# sjl.net
KiCad netlist of a schematic drawn in EasyEDA Pro
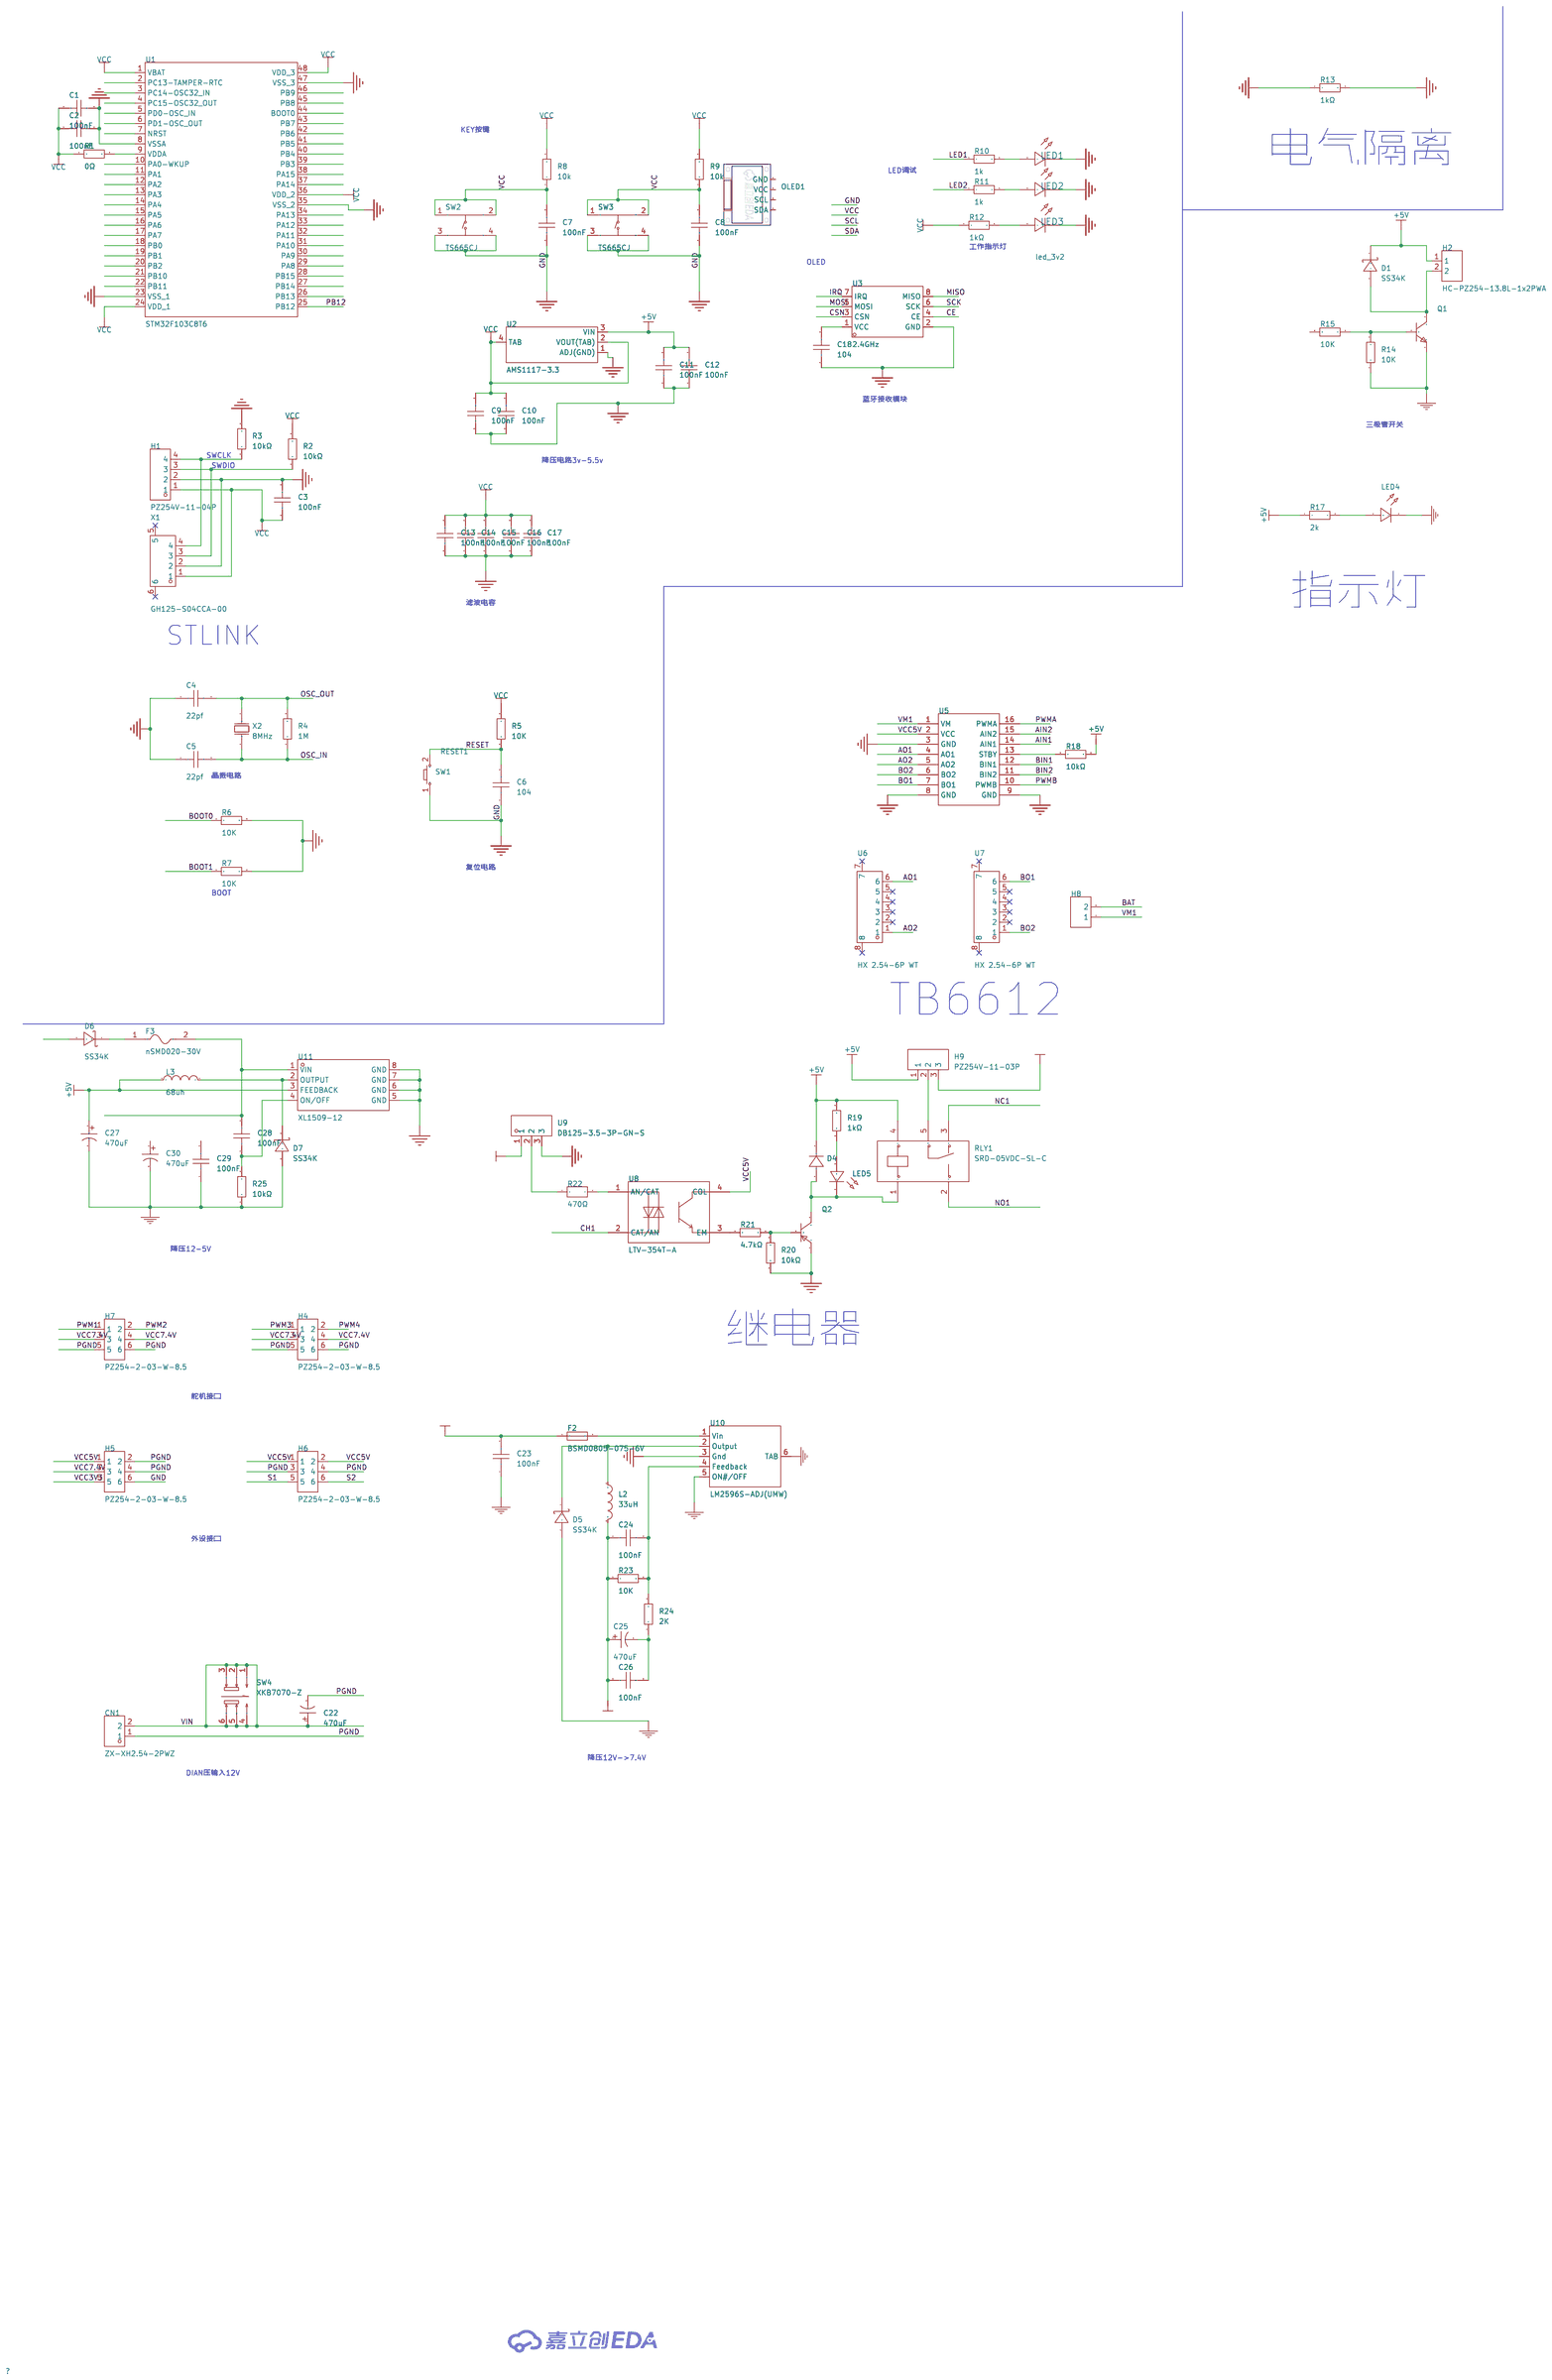
[diagram p0: schematic sheet]

(export (version "E")
  (design (tool "Eeschema 10.0.6"))
  (components
    (comp (ref "C1")
      (value "100nF")
      (footprint "easyedapro:C0603")
      (description "容值:100nF;精度:±10%;额定电压:50V;温度系数:X7R;")
      (fields
        (field (name "Manufacturer Part") "CGA0603X7R104K500JT")
        (field (name "Manufacturer") "HRE(芯声)")
      )
      (libsource (lib "easyedapro") (part "CGA0603X7R104K500JT"))
    )
    (comp (ref "C2")
      (value "100nF")
      (footprint "easyedapro:C0603")
      (description "容值:100nF;精度:±10%;额定电压:50V;温度系数:X7R;")
      (fields
        (field (name "Manufacturer Part") "CGA0603X7R104K500JT")
        (field (name "Manufacturer") "HRE(芯声)")
      )
      (libsource (lib "easyedapro") (part "CGA0603X7R104K500JT"))
    )
    (comp (ref "C3")
      (value "100nF")
      (footprint "easyedapro:C0603")
      (description "容值:100nF;精度:±10%;额定电压:50V;温度系数:X7R;")
      (fields
        (field (name "Manufacturer Part") "CGA0603X7R104K500JT")
        (field (name "Manufacturer") "HRE(芯声)")
      )
      (libsource (lib "easyedapro") (part "CGA0603X7R104K500JT"))
    )
    (comp (ref "C4")
      (value "22pf")
      (footprint "easyedapro:C0603")
      (libsource (lib "easyedapro") (part "CapAcitance"))
    )
    (comp (ref "C5")
      (value "22pf")
      (footprint "easyedapro:C0603")
      (libsource (lib "easyedapro") (part "CapAcitance"))
    )
    (comp (ref "C6")
      (value "104")
      (footprint "easyedapro:C0603")
      (description "容值:100nF;精度:±10%;额定电压:50V;温度系数:X7R;")
      (fields
        (field (name "Manufacturer Part") "CGA0603X7R104K500JT")
        (field (name "Manufacturer") "HRE(芯声)")
      )
      (libsource (lib "easyedapro") (part "CGA0603X7R104K500JT"))
    )
    (comp (ref "C7")
      (value "100nF")
      (footprint "easyedapro:C0603")
      (description "容值:100nF;精度:±10%;额定电压:50V;温度系数:X7R;")
      (fields
        (field (name "Manufacturer Part") "CGA0603X7R104K500JT")
        (field (name "Manufacturer") "HRE(芯声)")
      )
      (libsource (lib "easyedapro") (part "CGA0603X7R104K500JT"))
    )
    (comp (ref "C8")
      (value "100nF")
      (footprint "easyedapro:C0603")
      (description "容值:100nF;精度:±10%;额定电压:50V;温度系数:X7R;")
      (fields
        (field (name "Manufacturer Part") "CGA0603X7R104K500JT")
        (field (name "Manufacturer") "HRE(芯声)")
      )
      (libsource (lib "easyedapro") (part "CGA0603X7R104K500JT"))
    )
    (comp (ref "C9")
      (value "100nF")
      (footprint "easyedapro:C0603")
      (description "容值:100nF;精度:±10%;额定电压:50V;温度系数:X7R;")
      (fields
        (field (name "Manufacturer Part") "CGA0603X7R104K500JT")
        (field (name "Manufacturer") "HRE(芯声)")
      )
      (libsource (lib "easyedapro") (part "CGA0603X7R104K500JT"))
    )
    (comp (ref "C10")
      (value "100nF")
      (footprint "easyedapro:C0603")
      (description "容值:100nF;精度:±10%;额定电压:50V;温度系数:X7R;")
      (fields
        (field (name "Manufacturer Part") "CGA0603X7R104K500JT")
        (field (name "Manufacturer") "HRE(芯声)")
      )
      (libsource (lib "easyedapro") (part "CGA0603X7R104K500JT"))
    )
    (comp (ref "C11")
      (value "100nF")
      (footprint "easyedapro:C0603")
      (description "容值:100nF;精度:±10%;额定电压:50V;温度系数:X7R;")
      (fields
        (field (name "Manufacturer Part") "CGA0603X7R104K500JT")
        (field (name "Manufacturer") "HRE(芯声)")
      )
      (libsource (lib "easyedapro") (part "CGA0603X7R104K500JT"))
    )
    (comp (ref "C12")
      (value "100nF")
      (footprint "easyedapro:C0603")
      (description "容值:100nF;精度:±10%;额定电压:50V;温度系数:X7R;")
      (fields
        (field (name "Manufacturer Part") "CGA0603X7R104K500JT")
        (field (name "Manufacturer") "HRE(芯声)")
      )
      (libsource (lib "easyedapro") (part "CGA0603X7R104K500JT"))
    )
    (comp (ref "C13")
      (value "100nF")
      (footprint "easyedapro:C0603")
      (description "容值:100nF;精度:±10%;额定电压:50V;温度系数:X7R;")
      (fields
        (field (name "Manufacturer Part") "CGA0603X7R104K500JT")
        (field (name "Manufacturer") "HRE(芯声)")
      )
      (libsource (lib "easyedapro") (part "CGA0603X7R104K500JT"))
    )
    (comp (ref "C14")
      (value "100nF")
      (footprint "easyedapro:C0603")
      (description "容值:100nF;精度:±10%;额定电压:50V;温度系数:X7R;")
      (fields
        (field (name "Manufacturer Part") "CGA0603X7R104K500JT")
        (field (name "Manufacturer") "HRE(芯声)")
      )
      (libsource (lib "easyedapro") (part "CGA0603X7R104K500JT"))
    )
    (comp (ref "C15")
      (value "100nF")
      (footprint "easyedapro:C0603")
      (description "容值:100nF;精度:±10%;额定电压:50V;温度系数:X7R;")
      (fields
        (field (name "Manufacturer Part") "CGA0603X7R104K500JT")
        (field (name "Manufacturer") "HRE(芯声)")
      )
      (libsource (lib "easyedapro") (part "CGA0603X7R104K500JT"))
    )
    (comp (ref "C16")
      (value "100nF")
      (footprint "easyedapro:C0603")
      (description "容值:100nF;精度:±10%;额定电压:50V;温度系数:X7R;")
      (fields
        (field (name "Manufacturer Part") "CGA0603X7R104K500JT")
        (field (name "Manufacturer") "HRE(芯声)")
      )
      (libsource (lib "easyedapro") (part "CGA0603X7R104K500JT"))
    )
    (comp (ref "C17")
      (value "100nF")
      (footprint "easyedapro:C0603")
      (description "容值:100nF;精度:±10%;额定电压:50V;温度系数:X7R;")
      (fields
        (field (name "Manufacturer Part") "CGA0603X7R104K500JT")
        (field (name "Manufacturer") "HRE(芯声)")
      )
      (libsource (lib "easyedapro") (part "CGA0603X7R104K500JT"))
    )
    (comp (ref "C18")
      (value "104")
      (footprint "easyedapro:C0603")
      (description "容值:100nF;精度:±10%;额定电压:50V;温度系数:X7R;")
      (fields
        (field (name "Manufacturer Part") "CGA0603X7R104K500JT")
        (field (name "Manufacturer") "HRE(芯声)")
      )
      (libsource (lib "easyedapro") (part "CGA0603X7R104K500JT"))
    )
    (comp (ref "C22")
      (value "470uF")
      (footprint "easyedapro:CAP-SMD_BD10.0-L10.3-W10.3-FD")
      (description "容值:470uF;精度:±20%;额定电压:25V;纹波电流:286mA@120Hz;等效串联电阻(ESR):-;")
      (fields (field (name "Manufacturer Part") "RVT1E471M1010") (field (name "Manufacturer") "ROQANG(容强)"))
      (libsource (lib "easyedapro") (part "RVT1E471M1010"))
    )
    (comp (ref "C23")
      (value "100nF")
      (footprint "easyedapro:C0603")
      (libsource (lib "easyedapro") (part "CapAcitance"))
    )
    (comp (ref "C24")
      (value "100nF")
      (footprint "easyedapro:C0603")
      (libsource (lib "easyedapro") (part "CapAcitance"))
    )
    (comp (ref "C25")
      (value "470uF")
      (footprint "easyedapro:CAP-SMD_BD10.0-L10.3-W10.3-FD")
      (description "容值:470uF;精度:±20%;额定电压:25V;纹波电流:286mA@120Hz;等效串联电阻(ESR):-;")
      (fields (field (name "Manufacturer Part") "RVT1E471M1010") (field (name "Manufacturer") "ROQANG(容强)"))
      (libsource (lib "easyedapro") (part "RVT1E471M1010"))
    )
    (comp (ref "C26")
      (value "100nF")
      (footprint "easyedapro:C0603")
      (libsource (lib "easyedapro") (part "CapAcitance"))
    )
    (comp (ref "C27")
      (value "470uF")
      (footprint "easyedapro:CAP-SMD_BD10.0-L10.3-W10.3-FD")
      (description "容值:470uF;精度:±20%;额定电压:25V;纹波电流:286mA@120Hz;等效串联电阻(ESR):-;")
      (fields (field (name "Manufacturer Part") "RVT1E471M1010") (field (name "Manufacturer") "ROQANG(容强)"))
      (libsource (lib "easyedapro") (part "RVT1E471M1010"))
    )
    (comp (ref "C28")
      (value "100nF")
      (footprint "easyedapro:C0603")
      (libsource (lib "easyedapro") (part "CapAcitance"))
    )
    (comp (ref "C29")
      (value "100nF")
      (footprint "easyedapro:C0603")
      (libsource (lib "easyedapro") (part "CapAcitance"))
    )
    (comp (ref "C30")
      (value "470uF")
      (footprint "easyedapro:CAP-SMD_BD10.0-L10.3-W10.3-FD")
      (description "容值:470uF;精度:±20%;额定电压:25V;纹波电流:286mA@120Hz;等效串联电阻(ESR):-;")
      (fields (field (name "Manufacturer Part") "RVT1E471M1010") (field (name "Manufacturer") "ROQANG(容强)"))
      (libsource (lib "easyedapro") (part "RVT1E471M1010"))
    )
    (comp (ref "CN1")
      (value "ZX-XH2.54-2PWZ")
      (footprint "easyedapro:CONN-TH_2P-P2.50_ZX-XH2.54-2PWZ")
      (fields (field (name "Manufacturer") "Megastar(兆星)"))
      (libsource (lib "easyedapro") (part "ZX-XH2.54-2PWZ"))
    )
    (comp (ref "D1")
      (value "SS34K")
      (footprint "easyedapro:SMA_L4.3-W2.6-LS5.2-RD")
      (description "二极管配置:独立式;直流反向耐压(Vr):40V;平均整流电流(Io):3A;正向压降(Vf):550mV@3A;反向电流(Ir):500uA@40V;")
      (fields (field (name "Manufacturer") "TDD(台冠电子)"))
      (libsource (lib "easyedapro") (part "SS34K"))
    )
    (comp (ref "D4")
      (value "~")
      (footprint "easyedapro:DO_1N4007")
      (libsource (lib "easyedapro") (part "D_1N4007"))
    )
    (comp (ref "D5")
      (value "SS34K")
      (footprint "easyedapro:SMA_L4.3-W2.6-LS5.2-RD")
      (description "二极管配置:独立式;直流反向耐压(Vr):40V;平均整流电流(Io):3A;正向压降(Vf):550mV@3A;反向电流(Ir):500uA@40V;")
      (fields (field (name "Manufacturer") "TDD(台冠电子)"))
      (libsource (lib "easyedapro") (part "SS34K"))
    )
    (comp (ref "D6")
      (value "SS34K")
      (footprint "easyedapro:SMA_L4.3-W2.6-LS5.2-RD")
      (description "二极管配置:独立式;直流反向耐压(Vr):40V;平均整流电流(Io):3A;正向压降(Vf):550mV@3A;反向电流(Ir):500uA@40V;")
      (fields (field (name "Manufacturer") "TDD(台冠电子)"))
      (libsource (lib "easyedapro") (part "SS34K"))
    )
    (comp (ref "D7")
      (value "SS34K")
      (footprint "easyedapro:SMA_L4.3-W2.6-LS5.2-RD")
      (description "二极管配置:独立式;直流反向耐压(Vr):40V;平均整流电流(Io):3A;正向压降(Vf):550mV@3A;反向电流(Ir):500uA@40V;")
      (fields (field (name "Manufacturer") "TDD(台冠电子)"))
      (libsource (lib "easyedapro") (part "SS34K"))
    )
    (comp (ref "F2")
      (value "BSMD0805-075-6V")
      (footprint "easyedapro:F0805")
      (description "最大电压:6V;最大电流:40A;保持电流:750mA;跳闸电流:1.5A;")
      (fields (field (name "Manufacturer") "BHFUSE(佰宏)"))
      (libsource (lib "easyedapro") (part "BSMD0805-075-6V"))
    )
    (comp (ref "F3")
      (value "nSMD020-30V")
      (footprint "easyedapro:F1206")
      (description "耐压:30V;最大电流:100A;保持电流(Ih):200mA;跳闸电流:460mA;")
      (fields (field (name "Manufacturer") "台湾陆海"))
      (libsource (lib "easyedapro") (part "nSMD020-30V"))
    )
    (comp (ref "H1")
      (value "PZ254V-11-04P")
      (footprint "easyedapro:HDR-TH_4P-P2.54-V-M")
      (fields (field (name "Manufacturer") "XFCN(兴飞)"))
      (libsource (lib "easyedapro") (part "PZ254V-11-04P_C2691448"))
    )
    (comp (ref "H2")
      (value "HC-PZ254-13.8L-1x2PWA")
      (footprint "easyedapro:HDR-TH_2P-P2.54-H-M-W10.0")
      (fields (field (name "Manufacturer") "HC(虹成电子)"))
      (libsource (lib "easyedapro") (part "HC-PZ254-13.8L-1X2PWA"))
    )
    (comp (ref "H4")
      (value "PZ254-2-03-W-8.5")
      (footprint "easyedapro:HDR-TH_6P-P2.54-H-M-R2-C3-S2.54-W12.3-N")
      (fields (field (name "Manufacturer") "HCTL(华灿天禄)"))
      (libsource (lib "easyedapro") (part "PZ254-2-03-W-8.5"))
    )
    (comp (ref "H5")
      (value "PZ254-2-03-W-8.5")
      (footprint "easyedapro:HDR-TH_6P-P2.54-H-M-R2-C3-S2.54-W12.3-N")
      (fields (field (name "Manufacturer") "HCTL(华灿天禄)"))
      (libsource (lib "easyedapro") (part "PZ254-2-03-W-8.5"))
    )
    (comp (ref "H6")
      (value "PZ254-2-03-W-8.5")
      (footprint "easyedapro:HDR-TH_6P-P2.54-H-M-R2-C3-S2.54-W12.3-N")
      (fields (field (name "Manufacturer") "HCTL(华灿天禄)"))
      (libsource (lib "easyedapro") (part "PZ254-2-03-W-8.5"))
    )
    (comp (ref "H7")
      (value "PZ254-2-03-W-8.5")
      (footprint "easyedapro:HDR-TH_6P-P2.54-H-M-R2-C3-S2.54-W12.3-N")
      (fields (field (name "Manufacturer") "HCTL(华灿天禄)"))
      (libsource (lib "easyedapro") (part "PZ254-2-03-W-8.5"))
    )
    (comp (ref "H8")
      (value "~")
      (footprint "easyedapro:HDR-TH_2P-P2.54-V-F")
      (libsource (lib "easyedapro") (part "Header-Female-2.54_1x2"))
    )
    (comp (ref "H9")
      (value "PZ254V-11-03P")
      (footprint "easyedapro:HDR-TH_3P-P2.54-V-M")
      (fields (field (name "Manufacturer") "XFCN(兴飞)"))
      (libsource (lib "easyedapro") (part "PZ254V-11-03P_C2937625"))
    )
    (comp (ref "L2")
      (value "33uH")
      (footprint "easyedapro:L0603")
      (libsource (lib "easyedapro") (part "SDFL1608S100KTF"))
    )
    (comp (ref "L3")
      (value "68uh")
      (footprint "easyedapro:L0603")
      (libsource (lib "easyedapro") (part "SDFL1608S100KTF"))
    )
    (comp (ref "LED1")
      (value "~")
      (footprint "easyedapro:LED_0603")
      (libsource (lib "easyedapro") (part "LED_R"))
    )
    (comp (ref "LED2")
      (value "~")
      (footprint "easyedapro:LED_0603")
      (libsource (lib "easyedapro") (part "LED_R"))
    )
    (comp (ref "LED3")
      (value "led_3v2")
      (footprint "easyedapro:LED_0603")
      (libsource (lib "easyedapro") (part "LED_R"))
    )
    (comp (ref "LED4")
      (value "~")
      (footprint "easyedapro:LED_TH-3mm")
      (libsource (lib "easyedapro") (part "LED_TH-R"))
    )
    (comp (ref "LED5")
      (value "~")
      (footprint "easyedapro:LED_TH-3mm")
      (libsource (lib "easyedapro") (part "LED_TH-R"))
    )
    (comp (ref "OLED1")
      (value "~")
      (footprint "easyedapro:0.96OLED_4P")
      (libsource (lib "easyedapro") (part "0.96OLED模块_4P"))
    )
    (comp (ref "Q1")
      (value "~")
      (footprint "easyedapro:S8050_SOT-23")
      (libsource (lib "easyedapro") (part "NPN"))
    )
    (comp (ref "Q2")
      (value "~")
      (footprint "easyedapro:S8550P_SOT")
      (libsource (lib "easyedapro") (part "PNP"))
    )
    (comp (ref "R1")
      (value "0Ω")
      (footprint "easyedapro:R0603")
      (description "电阻类型:厚膜电阻;阻值:0Ω;精度:±1%;功率:100mW;最大工作电压:75V;")
      (fields
        (field (name "Manufacturer Part") "0603WAF0000T5E")
        (field (name "Manufacturer") "UNI-ROYAL(厚声)")
      )
      (libsource (lib "easyedapro") (part "0603WAF0000T5E"))
    )
    (comp (ref "R2")
      (value "10kΩ")
      (footprint "easyedapro:R0603")
      (description "电阻类型:厚膜电阻;阻值:10kΩ;精度:±1%;功率:100mW;最大工作电压:75V;温度系数:±100ppm/°C;")
      (fields
        (field (name "Manufacturer Part") "0603WAF1002T5E")
        (field (name "Manufacturer") "UNI-ROYAL(厚声)")
      )
      (libsource (lib "easyedapro") (part "0603WAF1002T5E"))
    )
    (comp (ref "R3")
      (value "10kΩ")
      (footprint "easyedapro:R0603")
      (description "电阻类型:厚膜电阻;阻值:10kΩ;精度:±1%;功率:100mW;最大工作电压:75V;温度系数:±100ppm/°C;")
      (fields
        (field (name "Manufacturer Part") "0603WAF1002T5E")
        (field (name "Manufacturer") "UNI-ROYAL(厚声)")
      )
      (libsource (lib "easyedapro") (part "0603WAF1002T5E"))
    )
    (comp (ref "R4")
      (value "1M")
      (footprint "easyedapro:R0603")
      (description "电阻类型:厚膜电阻;阻值:0Ω;精度:±1%;功率:100mW;最大工作电压:75V;")
      (fields
        (field (name "Manufacturer Part") "0603WAF0000T5E")
        (field (name "Manufacturer") "UNI-ROYAL(厚声)")
      )
      (libsource (lib "easyedapro") (part "0603WAF0000T5E"))
    )
    (comp (ref "R5")
      (value "10K")
      (footprint "easyedapro:R0603")
      (description "电阻类型:厚膜电阻;阻值:0Ω;精度:±1%;功率:100mW;最大工作电压:75V;")
      (fields
        (field (name "Manufacturer Part") "0603WAF0000T5E")
        (field (name "Manufacturer") "UNI-ROYAL(厚声)")
      )
      (libsource (lib "easyedapro") (part "0603WAF0000T5E"))
    )
    (comp (ref "R6")
      (value "10K")
      (footprint "easyedapro:Res_1/8W")
      (libsource (lib "easyedapro") (part "电阻"))
    )
    (comp (ref "R7")
      (value "10K")
      (footprint "easyedapro:Res_1/8W")
      (libsource (lib "easyedapro") (part "电阻"))
    )
    (comp (ref "R8")
      (value "10k")
      (footprint "easyedapro:R0603")
      (description "电阻类型:厚膜电阻;阻值:0Ω;精度:±1%;功率:100mW;最大工作电压:75V;")
      (fields
        (field (name "Manufacturer Part") "0603WAF0000T5E")
        (field (name "Manufacturer") "UNI-ROYAL(厚声)")
      )
      (libsource (lib "easyedapro") (part "0603WAF0000T5E"))
    )
    (comp (ref "R9")
      (value "10k")
      (footprint "easyedapro:R0603")
      (description "电阻类型:厚膜电阻;阻值:0Ω;精度:±1%;功率:100mW;最大工作电压:75V;")
      (fields
        (field (name "Manufacturer Part") "0603WAF0000T5E")
        (field (name "Manufacturer") "UNI-ROYAL(厚声)")
      )
      (libsource (lib "easyedapro") (part "0603WAF0000T5E"))
    )
    (comp (ref "R10")
      (value "1k")
      (footprint "easyedapro:R0603")
      (description "电阻类型:厚膜电阻;阻值:0Ω;精度:±1%;功率:100mW;最大工作电压:75V;")
      (fields
        (field (name "Manufacturer Part") "0603WAF0000T5E")
        (field (name "Manufacturer") "UNI-ROYAL(厚声)")
      )
      (libsource (lib "easyedapro") (part "0603WAF0000T5E"))
    )
    (comp (ref "R11")
      (value "1k")
      (footprint "easyedapro:R0603")
      (description "电阻类型:厚膜电阻;阻值:0Ω;精度:±1%;功率:100mW;最大工作电压:75V;")
      (fields
        (field (name "Manufacturer Part") "0603WAF0000T5E")
        (field (name "Manufacturer") "UNI-ROYAL(厚声)")
      )
      (libsource (lib "easyedapro") (part "0603WAF0000T5E"))
    )
    (comp (ref "R12")
      (value "1kΩ")
      (footprint "easyedapro:R0603")
      (description "电阻类型:厚膜电阻;阻值:1kΩ;精度:±1%;功率:100mW;最大工作电压:75V;温度系数:±100ppm/°C;")
      (fields
        (field (name "Manufacturer Part") "0603WAF1001T5E")
        (field (name "Manufacturer") "UNI-ROYAL(厚声)")
      )
      (libsource (lib "easyedapro") (part "0603WAF1001T5E"))
    )
    (comp (ref "R13")
      (value "1kΩ")
      (footprint "easyedapro:R0603")
      (description "电阻类型:厚膜电阻;阻值:1kΩ;精度:±1%;功率:100mW;最大工作电压:75V;温度系数:±100ppm/°C;")
      (fields
        (field (name "Manufacturer Part") "0603WAF1001T5E")
        (field (name "Manufacturer") "UNI-ROYAL(厚声)")
      )
      (libsource (lib "easyedapro") (part "0603WAF1001T5E"))
    )
    (comp (ref "R14")
      (value "10K")
      (footprint "easyedapro:Res_1/8W")
      (libsource (lib "easyedapro") (part "电阻"))
    )
    (comp (ref "R15")
      (value "10K")
      (footprint "easyedapro:Res_1/8W")
      (libsource (lib "easyedapro") (part "电阻"))
    )
    (comp (ref "R17")
      (value "2k")
      (footprint "easyedapro:Res_1/8W")
      (libsource (lib "easyedapro") (part "电阻"))
    )
    (comp (ref "R18")
      (value "10kΩ")
      (footprint "easyedapro:R0603")
      (description "电阻类型:厚膜电阻;阻值:10kΩ;精度:±1%;功率:100mW;最大工作电压:75V;温度系数:±100ppm/°C;")
      (fields
        (field (name "Manufacturer Part") "0603WAF1002T5E")
        (field (name "Manufacturer") "UNI-ROYAL(厚声)")
      )
      (libsource (lib "easyedapro") (part "0603WAF1002T5E"))
    )
    (comp (ref "R19")
      (value "1kΩ")
      (footprint "easyedapro:R0603")
      (description "电阻类型:厚膜电阻;阻值:1kΩ;精度:±1%;功率:100mW;最大工作电压:75V;温度系数:±100ppm/°C;")
      (fields
        (field (name "Manufacturer Part") "0603WAF1001T5E")
        (field (name "Manufacturer") "UNI-ROYAL(厚声)")
      )
      (libsource (lib "easyedapro") (part "0603WAF1001T5E"))
    )
    (comp (ref "R20")
      (value "10kΩ")
      (footprint "easyedapro:Res_1/8W")
      (libsource (lib "easyedapro") (part "电阻"))
    )
    (comp (ref "R21")
      (value "4.7kΩ")
      (footprint "easyedapro:R0603")
      (description "电阻类型:厚膜电阻;阻值:4.7kΩ;精度:±1%;功率:100mW;最大工作电压:75V;温度系数:±100ppm/°C;")
      (fields
        (field (name "Manufacturer Part") "0603WAF4701T5E")
        (field (name "Manufacturer") "UNI-ROYAL(厚声)")
      )
      (libsource (lib "easyedapro") (part "0603WAF4701T5E"))
    )
    (comp (ref "R22")
      (value "470Ω")
      (footprint "easyedapro:R0603")
      (description "电阻类型:厚膜电阻;阻值:470Ω;精度:±1%;功率:100mW;温度系数:±100ppm/°C;")
      (fields (field (name "Manufacturer Part") "CR164700F") (field (name "Manufacturer") "Meritek"))
      (libsource (lib "easyedapro") (part "CR164700F"))
    )
    (comp (ref "R23")
      (value "10K")
      (footprint "easyedapro:Res_1/8W")
      (libsource (lib "easyedapro") (part "电阻"))
    )
    (comp (ref "R24")
      (value "2K")
      (footprint "easyedapro:R0603")
      (description "电阻类型:厚膜电阻;阻值:4.7kΩ;精度:±1%;功率:100mW;最大工作电压:75V;温度系数:±100ppm/°C;")
      (fields
        (field (name "Manufacturer Part") "0603WAF4701T5E")
        (field (name "Manufacturer") "UNI-ROYAL(厚声)")
      )
      (libsource (lib "easyedapro") (part "0603WAF4701T5E"))
    )
    (comp (ref "R25")
      (value "10kΩ")
      (footprint "easyedapro:Res_1/8W")
      (libsource (lib "easyedapro") (part "电阻"))
    )
    (comp (ref "RLY1")
      (value "SRD-05VDC-SL-C")
      (footprint "easyedapro:RELAY-TH_SRD-XXVDC-XL-C")
      (description "线圈电压:5V;触点形式:一组转换:1C(单刀双掷-转换);触点容量(电阻负载):-;最大切换电压:250V@AC;最大切换电流:15A;")
      (fields (field (name "Manufacturer") "松乐"))
      (libsource (lib "easyedapro") (part "SRD-05VDC-SL-C"))
    )
    (comp (ref "SW1")
      (value "RESET1")
      (footprint "easyedapro:Key_SMD_3x4x2")
      (libsource (lib "easyedapro") (part "轻触按键x2"))
    )
    (comp (ref "SW2")
      (value "TS665CJ")
      (footprint "easyedapro:SW-TH_4P-L6.0-W6.0-P4.50-LS6.5")
      (description "电路结构:单刀单掷;按钮形状:圆形按钮;安装方式:直插;开关长度:6mm;开关宽度:6mm;开关高度:5mm;触点电流:50mA;额定电压(DC):12V;带灯:-;机械寿命:-;")
      (fields (field (name "Manufacturer") "SHOU HAN(首韩)"))
      (libsource (lib "easyedapro") (part "TS665CJ"))
    )
    (comp (ref "SW3")
      (value "TS665CJ")
      (footprint "easyedapro:SW-TH_4P-L6.0-W6.0-P4.50-LS6.5")
      (description "电路结构:单刀单掷;按钮形状:圆形按钮;安装方式:直插;开关长度:6mm;开关宽度:6mm;开关高度:5mm;触点电流:50mA;额定电压(DC):12V;带灯:-;机械寿命:-;")
      (fields (field (name "Manufacturer") "SHOU HAN(首韩)"))
      (libsource (lib "easyedapro") (part "TS665CJ"))
    )
    (comp (ref "SW4")
      (value "XKB7070-Z")
      (footprint "easyedapro:SW-TH_6P-L7.0-W7.0-P2.00")
      (description "自锁/无锁:自锁;安装方式:直插;触点电流:100mA;额定电压 (AC):250V;额定电压 (DC):30V;带灯:不带;作用力:160gf;机械寿命:10万次;")
      (fields (field (name "Manufacturer") "XKB Connectivity(中国星坤)"))
      (libsource (lib "easyedapro") (part "XKB7070-Z"))
    )
    (comp (ref "U1")
      (value "STM32F103C8T6")
      (footprint "easyedapro:LQFP-48_L7.0-W7.0-P0.50-LS9.0-BL")
      (description "CPU内核:ARM-M3;CPU最大主频:72MHz;应用领域:-;")
      (fields (field (name "Manufacturer") "ST(意法半导体)"))
      (libsource (lib "easyedapro") (part "STM32F103C8T6"))
    )
    (comp (ref "U2")
      (value "AMS1117-3.3")
      (footprint "easyedapro:SOT-223-4_L6.5-W3.5-P2.30-LS7.0-BR")
      (description "输出类型:固定;工作电压:12V;输出电压:3.3V;输出电流:1A;电源纹波抑制比(PSRR):60dB@(120Hz);输出极性:正极;")
      (fields (field (name "Manufacturer") "UMW(友台半导体)"))
      (libsource (lib "easyedapro") (part "AMS1117-3.3_C347222"))
    )
    (comp (ref "U3")
      (value "2.4GHz")
      (footprint "easyedapro:WIRELM-TH_NF-01-S")
      (description "模式:发射;频率:2.4GHz;天线形式:板载PCB天线;接收灵敏度:-96dBm;")
      (fields (field (name "Manufacturer Part") "NF-01-S") (field (name "Manufacturer") "Ai-Thinker(安信可)"))
      (libsource (lib "easyedapro") (part "NF-01-S"))
    )
    (comp (ref "U5") (value "~") (description "电机驱动") (libsource (lib "easyedapro") (part "TB6612")))
    (comp (ref "U6")
      (value "HX 2.54-6P WT")
      (footprint "easyedapro:CONN-SMD_6P-P2.50_HANXIA_HX-2.54-6P-WT")
      (description "插针结构:1x6P;间距:2.54mm;安装方式:卧贴;总PIN数:6P;排数:1;每排PIN数:6;额定电流:3A;工作温度范围:-25°C~+85°C;")
      (fields (field (name "Manufacturer") "hanxia(韩下)"))
      (libsource (lib "easyedapro") (part "HX 2.54-6P WT"))
    )
    (comp (ref "U7")
      (value "HX 2.54-6P WT")
      (footprint "easyedapro:CONN-SMD_6P-P2.50_HANXIA_HX-2.54-6P-WT")
      (description "插针结构:1x6P;间距:2.54mm;安装方式:卧贴;总PIN数:6P;排数:1;每排PIN数:6;额定电流:3A;工作温度范围:-25°C~+85°C;")
      (fields (field (name "Manufacturer") "hanxia(韩下)"))
      (libsource (lib "easyedapro") (part "HX 2.54-6P WT"))
    )
    (comp (ref "U8")
      (value "LTV-354T-A")
      (footprint "easyedapro:SOP-4_L3.9-W4.4-P2.54-LS7.0-TL")
      (fields (field (name "Manufacturer") "LITEON(光宝)"))
      (libsource (lib "easyedapro") (part "LTV-354T-A"))
    )
    (comp (ref "U9")
      (value "DB125-3.5-3P-GN-S")
      (footprint "easyedapro:CONN-TH_3P-P3.50_L7.4-W10.5")
      (fields (field (name "Manufacturer") "DORABO(地博电气)"))
      (libsource (lib "easyedapro") (part "DB125-3.5-3P-GN-S"))
    )
    (comp (ref "U10")
      (value "LM2596S-ADJ(UMW)")
      (footprint "easyedapro:TO-263-5_L10.2-W8.9-P1.70-BR")
      (description "功能类型:降压型;输出类型:可调;工作电压:40V;输出电压:1.2V~37V;输出电流:3A;")
      (fields (field (name "Manufacturer") "UMW(友台半导体)"))
      (libsource (lib "easyedapro") (part "LM2596S-ADJ"))
    )
    (comp (ref "U11")
      (value "XL1509-12")
      (footprint "easyedapro:SOIC-8_L4.9-W3.9-P1.27-LS6.0-BL")
      (description "功能类型:降压型;输出类型:固定;工作电压:4.5V~40V;输出电压:12V;输出电流:2A;")
      (fields (field (name "Manufacturer") "UMW(友台半导体)"))
      (libsource (lib "easyedapro") (part "XL1509-12"))
    )
    (comp (ref "X1")
      (value "GH125-S04CCA-00")
      (footprint "easyedapro:CONN-SMD_4P-P1.25_JS_GH125-S04CCA-00")
      (description "插针结构:1x4P;间距:1.25mm;安装方式:立贴;参考系列:-;总PIN数:4P;排数:1;每排PIN数:4;行距:-;额定电流:1A;工作温度范围:-25°C~+85°C;")
      (fields (field (name "Manufacturer") "JS(钜硕电子)"))
      (libsource (lib "easyedapro") (part "GH125-S04CCA-00"))
    )
    (comp (ref "X2")
      (value "8MHz")
      (footprint "easyedapro:CRYSTAL-SMD_L5.0-W3.2")
      (description "晶振类型:贴片晶振;频率:8MHz;常温频差:±10ppm;负载电容:20pF;频率稳定度:±20ppm;")
      (fields (field (name "Manufacturer Part") "X50328MSB2GI") (field (name "Manufacturer") "YXC(扬兴晶振)"))
      (libsource (lib "easyedapro") (part "X50328MSB2GI"))
    )
  )
  (nets
    (net (code "1") (name "+5V") (class "Default")
      (node (ref "C11") (pin "2") (pinfunction "2_2") (pintype "unspecified"))
      (node (ref "C12") (pin "2") (pinfunction "2_2") (pintype "unspecified"))
      (node (ref "C27") (pin "1") (pinfunction "1_1") (pintype "input"))
      (node (ref "D1") (pin "1") (pinfunction "C_1") (pintype "input"))
      (node (ref "D4") (pin "1") (pinfunction "K_1") (pintype "input"))
      (node (ref "H2") (pin "1") (pinfunction "1_1") (pintype "unspecified"))
      (node (ref "H9") (pin "1") (pinfunction "1_1") (pintype "unspecified"))
      (node (ref "L3") (pin "1") (pinfunction "1_1") (pintype "unspecified"))
      (node (ref "R17") (pin "1") (pinfunction "1_1") (pintype "input"))
      (node (ref "R18") (pin "2") (pinfunction "2_2") (pintype "input"))
      (node (ref "R19") (pin "2") (pinfunction "2_2") (pintype "input"))
      (node (ref "RLY1") (pin "4") (pinfunction "4_4") (pintype "input"))
      (node (ref "U11") (pin "3") (pinfunction "FEEDBACK_3") (pintype "unspecified"))
      (node (ref "U2") (pin "3") (pinfunction "VIN_3") (pintype "unspecified"))
    )
    (net (code "2") (name "/AIN1") (class "Default")
      (node (ref "U5") (pin "14") (pinfunction "AIN1_14") (pintype "input"))
    )
    (net (code "3") (name "/AIN2") (class "Default")
      (node (ref "U5") (pin "15") (pinfunction "AIN2_15") (pintype "input"))
    )
    (net (code "4") (name "/AO1") (class "Default")
      (node (ref "U5") (pin "4") (pinfunction "AO1_4") (pintype "input"))
      (node (ref "U6") (pin "6") (pinfunction "6_6") (pintype "unspecified"))
    )
    (net (code "5") (name "/AO2") (class "Default")
      (node (ref "U5") (pin "5") (pinfunction "AO2_5") (pintype "input"))
      (node (ref "U6") (pin "1") (pinfunction "1_1") (pintype "unspecified"))
    )
    (net (code "6") (name "/BIN1") (class "Default")
      (node (ref "U5") (pin "12") (pinfunction "BIN1_12") (pintype "input"))
    )
    (net (code "7") (name "/BIN2") (class "Default")
      (node (ref "U5") (pin "11") (pinfunction "BIN2_11") (pintype "input"))
    )
    (net (code "8") (name "/BO1") (class "Default")
      (node (ref "U5") (pin "7") (pinfunction "BO1_7") (pintype "input"))
      (node (ref "U7") (pin "6") (pinfunction "6_6") (pintype "unspecified"))
    )
    (net (code "9") (name "/BO2") (class "Default")
      (node (ref "U5") (pin "6") (pinfunction "BO2_6") (pintype "input"))
      (node (ref "U7") (pin "1") (pinfunction "1_1") (pintype "unspecified"))
    )
    (net (code "10") (name "/BOOT0") (class "Default")
      (node (ref "R6") (pin "1") (pinfunction "1_1") (pintype "input"))
    )
    (net (code "11") (name "/BOOT1") (class "Default")
      (node (ref "R7") (pin "1") (pinfunction "1_1") (pintype "input"))
    )
    (net (code "12") (name "/CE") (class "Default")
      (node (ref "U3") (pin "4") (pinfunction "CE_4") (pintype "unspecified"))
    )
    (net (code "13") (name "/CH1") (class "Default")
      (node (ref "U8") (pin "2") (pinfunction "CAT/AN_2") (pintype "unspecified"))
    )
    (net (code "14") (name "/CSN") (class "Default")
      (node (ref "U3") (pin "3") (pinfunction "CSN_3") (pintype "unspecified"))
    )
    (net (code "15") (name "/IRQ") (class "Default")
      (node (ref "U3") (pin "7") (pinfunction "IRQ_7") (pintype "unspecified"))
    )
    (net (code "16") (name "/LED1") (class "Default")
      (node (ref "R10") (pin "1") (pinfunction "1_1") (pintype "input"))
    )
    (net (code "17") (name "/LED2") (class "Default")
      (node (ref "R11") (pin "1") (pinfunction "1_1") (pintype "input"))
    )
    (net (code "18") (name "/MISO") (class "Default")
      (node (ref "U3") (pin "8") (pinfunction "MISO_8") (pintype "unspecified"))
    )
    (net (code "19") (name "/MOSI") (class "Default")
      (node (ref "U3") (pin "5") (pinfunction "MOSI_5") (pintype "unspecified"))
    )
    (net (code "20") (name "/NC1") (class "Default")
      (node (ref "RLY1") (pin "3") (pinfunction "3_3") (pintype "input"))
    )
    (net (code "21") (name "/NO1") (class "Default")
      (node (ref "RLY1") (pin "2") (pinfunction "2_2") (pintype "input"))
    )
    (net (code "22") (name "/OSC_IN") (class "Default")
      (node (ref "C5") (pin "2") (pinfunction "2_2") (pintype "input"))
      (node (ref "R4") (pin "1") (pinfunction "1_1") (pintype "input"))
      (node (ref "X2") (pin "2") (pinfunction "OSC2_2") (pintype "input"))
    )
    (net (code "23") (name "/OSC_OUT") (class "Default")
      (node (ref "C4") (pin "2") (pinfunction "2_2") (pintype "input"))
      (node (ref "R4") (pin "2") (pinfunction "2_2") (pintype "input"))
      (node (ref "X2") (pin "1") (pinfunction "OSC1_1") (pintype "input"))
    )
    (net (code "24") (name "/PB12") (class "Default")
      (node (ref "U1") (pin "25") (pinfunction "PB12_25") (pintype "unspecified"))
    )
    (net (code "25") (name "/PWM1") (class "Default")
      (node (ref "H7") (pin "1") (pinfunction "1_1") (pintype "unspecified"))
    )
    (net (code "26") (name "/PWM2") (class "Default")
      (node (ref "H7") (pin "2") (pinfunction "2_2") (pintype "unspecified"))
    )
    (net (code "27") (name "/PWM3") (class "Default")
      (node (ref "H4") (pin "1") (pinfunction "1_1") (pintype "unspecified"))
    )
    (net (code "28") (name "/PWM4") (class "Default")
      (node (ref "H4") (pin "2") (pinfunction "2_2") (pintype "unspecified"))
    )
    (net (code "29") (name "/PWMA") (class "Default")
      (node (ref "U5") (pin "16") (pinfunction "PWMA_16") (pintype "input"))
    )
    (net (code "30") (name "/PWMB") (class "Default")
      (node (ref "U5") (pin "10") (pinfunction "PWMB_10") (pintype "input"))
    )
    (net (code "31") (name "/RESET") (class "Default")
      (node (ref "C6") (pin "2") (pinfunction "2_2") (pintype "unspecified"))
      (node (ref "R5") (pin "2") (pinfunction "2_2") (pintype "input"))
      (node (ref "SW1") (pin "2") (pinfunction "2_2") (pintype "input"))
    )
    (net (code "32") (name "/S1") (class "Default")
      (node (ref "H6") (pin "5") (pinfunction "5_5") (pintype "unspecified"))
    )
    (net (code "33") (name "/S2") (class "Default")
      (node (ref "H6") (pin "6") (pinfunction "6_6") (pintype "unspecified"))
    )
    (net (code "34") (name "/SCK") (class "Default")
      (node (ref "U3") (pin "6") (pinfunction "SCK_6") (pintype "unspecified"))
    )
    (net (code "37") (name "/VCC3V3") (class "Default")
      (node (ref "H5") (pin "5") (pinfunction "5_5") (pintype "unspecified"))
    )
    (net (code "38") (name "/VCC5V") (class "Default")
      (node (ref "H5") (pin "1") (pinfunction "1_1") (pintype "unspecified"))
      (node (ref "H6") (pin "1") (pinfunction "1_1") (pintype "unspecified"))
      (node (ref "H6") (pin "2") (pinfunction "2_2") (pintype "unspecified"))
      (node (ref "U5") (pin "2") (pinfunction "VCC_2") (pintype "input"))
      (node (ref "U8") (pin "4") (pinfunction "COL_4") (pintype "unspecified"))
    )
    (net (code "39") (name "/VIN") (class "Default")
      (node (ref "C22") (pin "1") (pinfunction "1_1") (pintype "input"))
      (node (ref "CN1") (pin "2") (pinfunction "2_2") (pintype "unspecified"))
      (node (ref "SW4") (pin "1") (pinfunction "1_1") (pintype "unspecified"))
      (node (ref "SW4") (pin "2") (pinfunction "2_2") (pintype "unspecified"))
      (node (ref "SW4") (pin "3") (pinfunction "3_3") (pintype "unspecified"))
      (node (ref "SW4") (pin "4") (pinfunction "4_4") (pintype "unspecified"))
      (node (ref "SW4") (pin "5") (pinfunction "5_5") (pintype "unspecified"))
      (node (ref "SW4") (pin "6") (pinfunction "6_6") (pintype "unspecified"))
    )
    (net (code "40") (name "/VM1") (class "Default")
      (node (ref "H8") (pin "1") (pinfunction "1_1") (pintype "input"))
      (node (ref "U5") (pin "1") (pinfunction "VM_1") (pintype "input"))
    )
    (net (code "41") (name "BAT") (class "Default")
      (node (ref "C23") (pin "2") (pinfunction "2_2") (pintype "input"))
      (node (ref "F2") (pin "1") (pinfunction "1_1") (pintype "unspecified"))
      (node (ref "H8") (pin "2") (pinfunction "2_2") (pintype "input"))
      (node (ref "H9") (pin "3") (pinfunction "3_3") (pintype "unspecified"))
    )
    (net (code "42") (name "GND") (class "Default")
      (node (ref "C1") (pin "2") (pinfunction "2_2") (pintype "unspecified"))
      (node (ref "C10") (pin "1") (pinfunction "1_1") (pintype "unspecified"))
      (node (ref "C11") (pin "1") (pinfunction "1_1") (pintype "unspecified"))
      (node (ref "C12") (pin "1") (pinfunction "1_1") (pintype "unspecified"))
      (node (ref "C13") (pin "1") (pinfunction "1_1") (pintype "unspecified"))
      (node (ref "C14") (pin "1") (pinfunction "1_1") (pintype "unspecified"))
      (node (ref "C15") (pin "1") (pinfunction "1_1") (pintype "unspecified"))
      (node (ref "C16") (pin "1") (pinfunction "1_1") (pintype "unspecified"))
      (node (ref "C17") (pin "1") (pinfunction "1_1") (pintype "unspecified"))
      (node (ref "C18") (pin "1") (pinfunction "1_1") (pintype "unspecified"))
      (node (ref "C2") (pin "2") (pinfunction "2_2") (pintype "unspecified"))
      (node (ref "C3") (pin "1") (pinfunction "1_1") (pintype "unspecified"))
      (node (ref "C4") (pin "1") (pinfunction "1_1") (pintype "input"))
      (node (ref "C5") (pin "1") (pinfunction "1_1") (pintype "input"))
      (node (ref "C6") (pin "1") (pinfunction "1_1") (pintype "unspecified"))
      (node (ref "C7") (pin "1") (pinfunction "1_1") (pintype "unspecified"))
      (node (ref "C8") (pin "1") (pinfunction "1_1") (pintype "unspecified"))
      (node (ref "C9") (pin "1") (pinfunction "1_1") (pintype "unspecified"))
      (node (ref "H1") (pin "2") (pinfunction "2_2") (pintype "unspecified"))
      (node (ref "H5") (pin "6") (pinfunction "6_6") (pintype "unspecified"))
      (node (ref "LED1") (pin "1") (pinfunction "C_1") (pintype "input"))
      (node (ref "LED2") (pin "1") (pinfunction "C_1") (pintype "input"))
      (node (ref "LED3") (pin "1") (pinfunction "C_1") (pintype "input"))
      (node (ref "R13") (pin "1") (pinfunction "1_1") (pintype "input"))
      (node (ref "R13") (pin "2") (pinfunction "2_2") (pintype "input"))
      (node (ref "R3") (pin "2") (pinfunction "2_2") (pintype "input"))
      (node (ref "R6") (pin "2") (pinfunction "2_2") (pintype "input"))
      (node (ref "R7") (pin "2") (pinfunction "2_2") (pintype "input"))
      (node (ref "SW1") (pin "1") (pinfunction "1_1") (pintype "input"))
      (node (ref "SW2") (pin "3") (pinfunction "C_3") (pintype "unspecified"))
      (node (ref "SW2") (pin "4") (pinfunction "D_4") (pintype "unspecified"))
      (node (ref "SW3") (pin "3") (pinfunction "C_3") (pintype "unspecified"))
      (node (ref "SW3") (pin "4") (pinfunction "D_4") (pintype "unspecified"))
      (node (ref "U1") (pin "23") (pinfunction "VSS_1_23") (pintype "unspecified"))
      (node (ref "U1") (pin "35") (pinfunction "VSS_2_35") (pintype "unspecified"))
      (node (ref "U1") (pin "47") (pinfunction "VSS_3_47") (pintype "unspecified"))
      (node (ref "U1") (pin "8") (pinfunction "VSSA_8") (pintype "unspecified"))
      (node (ref "U10") (pin "3") (pinfunction "Gnd_3") (pintype "unspecified"))
      (node (ref "U11") (pin "5") (pinfunction "GND_5") (pintype "unspecified"))
      (node (ref "U11") (pin "6") (pinfunction "GND_6") (pintype "unspecified"))
      (node (ref "U11") (pin "7") (pinfunction "GND_7") (pintype "unspecified"))
      (node (ref "U11") (pin "8") (pinfunction "GND_8") (pintype "unspecified"))
      (node (ref "U2") (pin "1") (pinfunction "ADJ(GND)_1") (pintype "unspecified"))
      (node (ref "U3") (pin "2") (pinfunction "GND_2") (pintype "unspecified"))
      (node (ref "U5") (pin "3") (pinfunction "GND_3") (pintype "input"))
      (node (ref "U5") (pin "8") (pinfunction "GND_8") (pintype "input"))
      (node (ref "U5") (pin "9") (pinfunction "GND_9") (pintype "input"))
      (node (ref "U9") (pin "3") (pinfunction "3_3") (pintype "unspecified"))
      (node (ref "X1") (pin "2") (pinfunction "2_2") (pintype "unspecified"))
    )
    (net (code "43") (name "Net-(C25-Pad2)") (class "Default")
      (node (ref "C25") (pin "2") (pinfunction "2_2") (pintype "input"))
      (node (ref "C26") (pin "2") (pinfunction "2_2") (pintype "input"))
      (node (ref "R24") (pin "1") (pinfunction "1_1") (pintype "input"))
    )
    (net (code "44") (name "Net-(D1-A)") (class "Default")
      (node (ref "D1") (pin "2") (pinfunction "A_2") (pintype "input"))
      (node (ref "H2") (pin "2") (pinfunction "2_2") (pintype "unspecified"))
      (node (ref "Q1") (pin "3") (pinfunction "3_3") (pintype "unspecified"))
    )
    (net (code "45") (name "Net-(D4-A)") (class "Default")
      (node (ref "D4") (pin "2") (pinfunction "A_2") (pintype "input"))
      (node (ref "LED5") (pin "2") (pinfunction "A_2") (pintype "input"))
      (node (ref "Q2") (pin "3") (pinfunction "C_3") (pintype "input"))
      (node (ref "RLY1") (pin "1") (pinfunction "1_1") (pintype "input"))
    )
    (net (code "46") (name "Net-(D5-C)") (class "Default")
      (node (ref "D5") (pin "1") (pinfunction "C_1") (pintype "input"))
      (node (ref "L2") (pin "1") (pinfunction "1_1") (pintype "unspecified"))
      (node (ref "U10") (pin "2") (pinfunction "Output_2") (pintype "unspecified"))
    )
    (net (code "47") (name "Net-(D6-C)") (class "Default")
      (node (ref "D6") (pin "1") (pinfunction "C_1") (pintype "input"))
      (node (ref "F3") (pin "1") (pinfunction "1_1") (pintype "unspecified"))
    )
    (net (code "48") (name "Net-(D7-C)") (class "Default")
      (node (ref "D7") (pin "1") (pinfunction "C_1") (pintype "input"))
      (node (ref "L3") (pin "2") (pinfunction "2_2") (pintype "unspecified"))
      (node (ref "U11") (pin "2") (pinfunction "OUTPUT_2") (pintype "unspecified"))
    )
    (net (code "49") (name "Net-(H1-Pad3)") (class "Default")
      (node (ref "H1") (pin "3") (pinfunction "3_3") (pintype "unspecified"))
      (node (ref "R2") (pin "1") (pinfunction "1_1") (pintype "input"))
      (node (ref "X1") (pin "3") (pinfunction "3_3") (pintype "unspecified"))
    )
    (net (code "50") (name "Net-(H1-Pad4)") (class "Default")
      (node (ref "H1") (pin "4") (pinfunction "4_4") (pintype "unspecified"))
      (node (ref "R3") (pin "1") (pinfunction "1_1") (pintype "input"))
      (node (ref "X1") (pin "4") (pinfunction "4_4") (pintype "unspecified"))
    )
    (net (code "51") (name "Net-(H9-Pad2)") (class "Default")
      (node (ref "H9") (pin "2") (pinfunction "2_2") (pintype "unspecified"))
      (node (ref "RLY1") (pin "5") (pinfunction "5_5") (pintype "input"))
    )
    (net (code "52") (name "Net-(LED1-A)") (class "Default")
      (node (ref "LED1") (pin "2") (pinfunction "A_2") (pintype "input"))
      (node (ref "R10") (pin "2") (pinfunction "2_2") (pintype "input"))
    )
    (net (code "53") (name "Net-(LED2-A)") (class "Default")
      (node (ref "LED2") (pin "2") (pinfunction "A_2") (pintype "input"))
      (node (ref "R11") (pin "2") (pinfunction "2_2") (pintype "input"))
    )
    (net (code "54") (name "Net-(LED3-A)") (class "Default")
      (node (ref "LED3") (pin "2") (pinfunction "A_2") (pintype "input"))
      (node (ref "R12") (pin "2") (pinfunction "2_2") (pintype "input"))
    )
    (net (code "55") (name "Net-(LED4-C)") (class "Default")
      (node (ref "LED4") (pin "1") (pinfunction "C_1") (pintype "input"))
      (node (ref "R17") (pin "2") (pinfunction "2_2") (pintype "input"))
    )
    (net (code "56") (name "Net-(LED5-C)") (class "Default")
      (node (ref "LED5") (pin "1") (pinfunction "C_1") (pintype "input"))
      (node (ref "R19") (pin "1") (pinfunction "1_1") (pintype "input"))
    )
    (net (code "57") (name "Net-(Q1-Pad1)") (class "Default")
      (node (ref "Q1") (pin "1") (pinfunction "1_1") (pintype "unspecified"))
      (node (ref "R14") (pin "2") (pinfunction "2_2") (pintype "input"))
      (node (ref "R15") (pin "1") (pinfunction "1_1") (pintype "input"))
    )
    (net (code "58") (name "Net-(Q2-B)") (class "Default")
      (node (ref "Q2") (pin "1") (pinfunction "B_1") (pintype "input"))
      (node (ref "R20") (pin "2") (pinfunction "2_2") (pintype "input"))
      (node (ref "R21") (pin "2") (pinfunction "2_2") (pintype "input"))
    )
    (net (code "59") (name "Net-(R22-Pad1)") (class "Default")
      (node (ref "R22") (pin "1") (pinfunction "1_1") (pintype "unspecified"))
      (node (ref "U9") (pin "2") (pinfunction "2_2") (pintype "unspecified"))
    )
    (net (code "60") (name "Net-(U1-VDDA)") (class "Default")
      (node (ref "R1") (pin "2") (pinfunction "2_2") (pintype "input"))
      (node (ref "U1") (pin "9") (pinfunction "VDDA_9") (pintype "unspecified"))
    )
    (net (code "61") (name "Net-(U3-VCC)") (class "Default")
      (node (ref "C18") (pin "2") (pinfunction "2_2") (pintype "unspecified"))
      (node (ref "U3") (pin "1") (pinfunction "VCC_1") (pintype "unspecified"))
    )
    (net (code "62") (name "Net-(U5-STBY)") (class "Default")
      (node (ref "R18") (pin "1") (pinfunction "1_1") (pintype "input"))
      (node (ref "U5") (pin "13") (pinfunction "STBY_13") (pintype "input"))
    )
    (net (code "63") (name "Net-(U8-AN{slash}CAT)") (class "Default")
      (node (ref "R22") (pin "2") (pinfunction "2_2") (pintype "unspecified"))
      (node (ref "U8") (pin "1") (pinfunction "AN/CAT_1") (pintype "unspecified"))
    )
    (net (code "64") (name "Net-(U8-EM)") (class "Default")
      (node (ref "R21") (pin "1") (pinfunction "1_1") (pintype "input"))
      (node (ref "U8") (pin "3") (pinfunction "EM_3") (pintype "unspecified"))
    )
    (net (code "65") (name "Net-(U10-Feedback)") (class "Default")
      (node (ref "C24") (pin "2") (pinfunction "2_2") (pintype "input"))
      (node (ref "R23") (pin "2") (pinfunction "2_2") (pintype "input"))
      (node (ref "R24") (pin "2") (pinfunction "2_2") (pintype "input"))
      (node (ref "U10") (pin "4") (pinfunction "Feedback_4") (pintype "unspecified"))
    )
    (net (code "66") (name "Net-(U10-Vin)") (class "Default")
      (node (ref "F2") (pin "2") (pinfunction "2_2") (pintype "unspecified"))
      (node (ref "U10") (pin "1") (pinfunction "Vin_1") (pintype "unspecified"))
    )
    (net (code "67") (name "Net-(U11-ON{slash}OFF)") (class "Default")
      (node (ref "C28") (pin "1") (pinfunction "1_1") (pintype "input"))
      (node (ref "R25") (pin "2") (pinfunction "2_2") (pintype "input"))
      (node (ref "U11") (pin "4") (pinfunction "ON/OFF_4") (pintype "unspecified"))
    )
    (net (code "68") (name "Net-(U11-VIN)") (class "Default")
      (node (ref "C28") (pin "2") (pinfunction "2_2") (pintype "input"))
      (node (ref "F3") (pin "2") (pinfunction "2_2") (pintype "unspecified"))
      (node (ref "U11") (pin "1") (pinfunction "VIN_1") (pintype "unspecified"))
    )
    (net (code "69") (name "PGND") (class "Default")
      (node (ref "C22") (pin "2") (pinfunction "2_2") (pintype "input"))
      (node (ref "C23") (pin "1") (pinfunction "1_1") (pintype "input"))
      (node (ref "C27") (pin "2") (pinfunction "2_2") (pintype "input"))
      (node (ref "C29") (pin "1") (pinfunction "1_1") (pintype "input"))
      (node (ref "C30") (pin "2") (pinfunction "2_2") (pintype "input"))
      (node (ref "CN1") (pin "1") (pinfunction "1_1") (pintype "unspecified"))
      (node (ref "D5") (pin "2") (pinfunction "A_2") (pintype "input"))
      (node (ref "D7") (pin "2") (pinfunction "A_2") (pintype "input"))
      (node (ref "H4") (pin "5") (pinfunction "5_5") (pintype "unspecified"))
      (node (ref "H4") (pin "6") (pinfunction "6_6") (pintype "unspecified"))
      (node (ref "H5") (pin "2") (pinfunction "2_2") (pintype "unspecified"))
      (node (ref "H5") (pin "4") (pinfunction "4_4") (pintype "unspecified"))
      (node (ref "H6") (pin "3") (pinfunction "3_3") (pintype "unspecified"))
      (node (ref "H6") (pin "4") (pinfunction "4_4") (pintype "unspecified"))
      (node (ref "H7") (pin "5") (pinfunction "5_5") (pintype "unspecified"))
      (node (ref "H7") (pin "6") (pinfunction "6_6") (pintype "unspecified"))
      (node (ref "LED4") (pin "2") (pinfunction "A_2") (pintype "input"))
      (node (ref "Q1") (pin "2") (pinfunction "2_2") (pintype "unspecified"))
      (node (ref "Q2") (pin "2") (pinfunction "E_2") (pintype "input"))
      (node (ref "R14") (pin "1") (pinfunction "1_1") (pintype "input"))
      (node (ref "R20") (pin "1") (pinfunction "1_1") (pintype "input"))
      (node (ref "R25") (pin "1") (pinfunction "1_1") (pintype "input"))
      (node (ref "U10") (pin "5") (pinfunction "ON#/OFF_5") (pintype "unspecified"))
      (node (ref "U10") (pin "6") (pinfunction "TAB_6") (pintype "unspecified"))
    )
    (net (code "70") (name "VCC") (class "Default")
      (node (ref "C1") (pin "1") (pinfunction "1_1") (pintype "unspecified"))
      (node (ref "C10") (pin "2") (pinfunction "2_2") (pintype "unspecified"))
      (node (ref "C13") (pin "2") (pinfunction "2_2") (pintype "unspecified"))
      (node (ref "C14") (pin "2") (pinfunction "2_2") (pintype "unspecified"))
      (node (ref "C15") (pin "2") (pinfunction "2_2") (pintype "unspecified"))
      (node (ref "C16") (pin "2") (pinfunction "2_2") (pintype "unspecified"))
      (node (ref "C17") (pin "2") (pinfunction "2_2") (pintype "unspecified"))
      (node (ref "C2") (pin "1") (pinfunction "1_1") (pintype "unspecified"))
      (node (ref "C3") (pin "2") (pinfunction "2_2") (pintype "unspecified"))
      (node (ref "C7") (pin "2") (pinfunction "2_2") (pintype "unspecified"))
      (node (ref "C8") (pin "2") (pinfunction "2_2") (pintype "unspecified"))
      (node (ref "C9") (pin "2") (pinfunction "2_2") (pintype "unspecified"))
      (node (ref "H1") (pin "1") (pinfunction "1_1") (pintype "unspecified"))
      (node (ref "R1") (pin "1") (pinfunction "1_1") (pintype "input"))
      (node (ref "R12") (pin "1") (pinfunction "1_1") (pintype "input"))
      (node (ref "R2") (pin "2") (pinfunction "2_2") (pintype "input"))
      (node (ref "R5") (pin "1") (pinfunction "1_1") (pintype "input"))
      (node (ref "R8") (pin "1") (pinfunction "1_1") (pintype "input"))
      (node (ref "R8") (pin "2") (pinfunction "2_2") (pintype "input"))
      (node (ref "R9") (pin "1") (pinfunction "1_1") (pintype "input"))
      (node (ref "R9") (pin "2") (pinfunction "2_2") (pintype "input"))
      (node (ref "SW2") (pin "1") (pinfunction "A_1") (pintype "unspecified"))
      (node (ref "SW2") (pin "2") (pinfunction "B_2") (pintype "unspecified"))
      (node (ref "SW3") (pin "1") (pinfunction "A_1") (pintype "unspecified"))
      (node (ref "SW3") (pin "2") (pinfunction "B_2") (pintype "unspecified"))
      (node (ref "U1") (pin "1") (pinfunction "VBAT_1") (pintype "unspecified"))
      (node (ref "U1") (pin "24") (pinfunction "VDD_1_24") (pintype "unspecified"))
      (node (ref "U1") (pin "36") (pinfunction "VDD_2_36") (pintype "unspecified"))
      (node (ref "U1") (pin "48") (pinfunction "VDD_3_48") (pintype "unspecified"))
      (node (ref "U2") (pin "2") (pinfunction "VOUT(TAB)_2") (pintype "unspecified"))
      (node (ref "U2") (pin "4") (pinfunction "TAB_4") (pintype "unspecified"))
      (node (ref "X1") (pin "1") (pinfunction "1_1") (pintype "unspecified"))
    )
    (net (code "71") (name "VCC7.4V") (class "Default")
      (node (ref "C24") (pin "1") (pinfunction "1_1") (pintype "input"))
      (node (ref "C25") (pin "1") (pinfunction "1_1") (pintype "input"))
      (node (ref "C26") (pin "1") (pinfunction "1_1") (pintype "input"))
      (node (ref "H4") (pin "3") (pinfunction "3_3") (pintype "unspecified"))
      (node (ref "H4") (pin "4") (pinfunction "4_4") (pintype "unspecified"))
      (node (ref "H5") (pin "3") (pinfunction "3_3") (pintype "unspecified"))
      (node (ref "H7") (pin "3") (pinfunction "3_3") (pintype "unspecified"))
      (node (ref "H7") (pin "4") (pinfunction "4_4") (pintype "unspecified"))
      (node (ref "L2") (pin "2") (pinfunction "2_2") (pintype "unspecified"))
      (node (ref "R23") (pin "1") (pinfunction "1_1") (pintype "input"))
    )
    (net (code "72") (name "VCCC3V3") (class "Default")
      (node (ref "U9") (pin "1") (pinfunction "1_1") (pintype "unspecified"))
    )
    (net (code "73") (name "unconnected-(C29-Pad2)") (class "Default")
      (node (ref "C29") (pin "2") (pinfunction "2_2") (pintype "input"))
    )
    (net (code "74") (name "unconnected-(C30-Pad1)") (class "Default")
      (node (ref "C30") (pin "1") (pinfunction "1_1") (pintype "input"))
    )
    (net (code "75") (name "unconnected-(D6-A-Pad2)") (class "Default")
      (node (ref "D6") (pin "2") (pinfunction "A_2") (pintype "input"))
    )
    (net (code "76") (name "unconnected-(OLED1-GND-Pad1)") (class "Default")
      (node (ref "OLED1") (pin "1") (pinfunction "GND_1") (pintype "input"))
    )
    (net (code "77") (name "unconnected-(OLED1-SCL-Pad3)") (class "Default")
      (node (ref "OLED1") (pin "3") (pinfunction "SCL_3") (pintype "input"))
    )
    (net (code "78") (name "unconnected-(OLED1-SDA-Pad4)") (class "Default")
      (node (ref "OLED1") (pin "4") (pinfunction "SDA_4") (pintype "input"))
    )
    (net (code "79") (name "unconnected-(OLED1-VCC-Pad2)") (class "Default")
      (node (ref "OLED1") (pin "2") (pinfunction "VCC_2") (pintype "input"))
    )
    (net (code "80") (name "unconnected-(R15-Pad2)") (class "Default")
      (node (ref "R15") (pin "2") (pinfunction "2_2") (pintype "input"))
    )
    (net (code "81") (name "unconnected-(U1-BOOT0-Pad44)") (class "Default")
      (node (ref "U1") (pin "44") (pinfunction "BOOT0_44") (pintype "unspecified"))
    )
    (net (code "82") (name "unconnected-(U1-NRST-Pad7)") (class "Default")
      (node (ref "U1") (pin "7") (pinfunction "NRST_7") (pintype "unspecified"))
    )
    (net (code "83") (name "unconnected-(U1-PA0-WKUP-Pad10)") (class "Default")
      (node (ref "U1") (pin "10") (pinfunction "PA0-WKUP_10") (pintype "unspecified"))
    )
    (net (code "84") (name "unconnected-(U1-PA1-Pad11)") (class "Default")
      (node (ref "U1") (pin "11") (pinfunction "PA1_11") (pintype "unspecified"))
    )
    (net (code "85") (name "unconnected-(U1-PA2-Pad12)") (class "Default")
      (node (ref "U1") (pin "12") (pinfunction "PA2_12") (pintype "unspecified"))
    )
    (net (code "86") (name "unconnected-(U1-PA3-Pad13)") (class "Default")
      (node (ref "U1") (pin "13") (pinfunction "PA3_13") (pintype "unspecified"))
    )
    (net (code "87") (name "unconnected-(U1-PA4-Pad14)") (class "Default")
      (node (ref "U1") (pin "14") (pinfunction "PA4_14") (pintype "unspecified"))
    )
    (net (code "88") (name "unconnected-(U1-PA5-Pad15)") (class "Default")
      (node (ref "U1") (pin "15") (pinfunction "PA5_15") (pintype "unspecified"))
    )
    (net (code "89") (name "unconnected-(U1-PA6-Pad16)") (class "Default")
      (node (ref "U1") (pin "16") (pinfunction "PA6_16") (pintype "unspecified"))
    )
    (net (code "90") (name "unconnected-(U1-PA7-Pad17)") (class "Default")
      (node (ref "U1") (pin "17") (pinfunction "PA7_17") (pintype "unspecified"))
    )
    (net (code "91") (name "unconnected-(U1-PA8-Pad29)") (class "Default")
      (node (ref "U1") (pin "29") (pinfunction "PA8_29") (pintype "unspecified"))
    )
    (net (code "92") (name "unconnected-(U1-PA9-Pad30)") (class "Default")
      (node (ref "U1") (pin "30") (pinfunction "PA9_30") (pintype "unspecified"))
    )
    (net (code "93") (name "unconnected-(U1-PA10-Pad31)") (class "Default")
      (node (ref "U1") (pin "31") (pinfunction "PA10_31") (pintype "unspecified"))
    )
    (net (code "94") (name "unconnected-(U1-PA11-Pad32)") (class "Default")
      (node (ref "U1") (pin "32") (pinfunction "PA11_32") (pintype "unspecified"))
    )
    (net (code "95") (name "unconnected-(U1-PA12-Pad33)") (class "Default")
      (node (ref "U1") (pin "33") (pinfunction "PA12_33") (pintype "unspecified"))
    )
    (net (code "96") (name "unconnected-(U1-PA13-Pad34)") (class "Default")
      (node (ref "U1") (pin "34") (pinfunction "PA13_34") (pintype "unspecified"))
    )
    (net (code "97") (name "unconnected-(U1-PA14-Pad37)") (class "Default")
      (node (ref "U1") (pin "37") (pinfunction "PA14_37") (pintype "unspecified"))
    )
    (net (code "98") (name "unconnected-(U1-PA15-Pad38)") (class "Default")
      (node (ref "U1") (pin "38") (pinfunction "PA15_38") (pintype "unspecified"))
    )
    (net (code "99") (name "unconnected-(U1-PB0-Pad18)") (class "Default")
      (node (ref "U1") (pin "18") (pinfunction "PB0_18") (pintype "unspecified"))
    )
    (net (code "100") (name "unconnected-(U1-PB1-Pad19)") (class "Default")
      (node (ref "U1") (pin "19") (pinfunction "PB1_19") (pintype "unspecified"))
    )
    (net (code "101") (name "unconnected-(U1-PB2-Pad20)") (class "Default")
      (node (ref "U1") (pin "20") (pinfunction "PB2_20") (pintype "unspecified"))
    )
    (net (code "102") (name "unconnected-(U1-PB3-Pad39)") (class "Default")
      (node (ref "U1") (pin "39") (pinfunction "PB3_39") (pintype "unspecified"))
    )
    (net (code "103") (name "unconnected-(U1-PB4-Pad40)") (class "Default")
      (node (ref "U1") (pin "40") (pinfunction "PB4_40") (pintype "unspecified"))
    )
    (net (code "104") (name "unconnected-(U1-PB5-Pad41)") (class "Default")
      (node (ref "U1") (pin "41") (pinfunction "PB5_41") (pintype "unspecified"))
    )
    (net (code "105") (name "unconnected-(U1-PB6-Pad42)") (class "Default")
      (node (ref "U1") (pin "42") (pinfunction "PB6_42") (pintype "unspecified"))
    )
    (net (code "106") (name "unconnected-(U1-PB7-Pad43)") (class "Default")
      (node (ref "U1") (pin "43") (pinfunction "PB7_43") (pintype "unspecified"))
    )
    (net (code "107") (name "unconnected-(U1-PB8-Pad45)") (class "Default")
      (node (ref "U1") (pin "45") (pinfunction "PB8_45") (pintype "unspecified"))
    )
    (net (code "108") (name "unconnected-(U1-PB9-Pad46)") (class "Default")
      (node (ref "U1") (pin "46") (pinfunction "PB9_46") (pintype "unspecified"))
    )
    (net (code "109") (name "unconnected-(U1-PB10-Pad21)") (class "Default")
      (node (ref "U1") (pin "21") (pinfunction "PB10_21") (pintype "unspecified"))
    )
    (net (code "110") (name "unconnected-(U1-PB11-Pad22)") (class "Default")
      (node (ref "U1") (pin "22") (pinfunction "PB11_22") (pintype "unspecified"))
    )
    (net (code "111") (name "unconnected-(U1-PB13-Pad26)") (class "Default")
      (node (ref "U1") (pin "26") (pinfunction "PB13_26") (pintype "unspecified"))
    )
    (net (code "112") (name "unconnected-(U1-PB14-Pad27)") (class "Default")
      (node (ref "U1") (pin "27") (pinfunction "PB14_27") (pintype "unspecified"))
    )
    (net (code "113") (name "unconnected-(U1-PB15-Pad28)") (class "Default")
      (node (ref "U1") (pin "28") (pinfunction "PB15_28") (pintype "unspecified"))
    )
    (net (code "114") (name "unconnected-(U1-PC13-TAMPER-RTC-Pad2)") (class "Default")
      (node (ref "U1") (pin "2") (pinfunction "PC13-TAMPER-RTC_2") (pintype "unspecified"))
    )
    (net (code "115") (name "unconnected-(U1-PC14-OSC32_IN-Pad3)") (class "Default")
      (node (ref "U1") (pin "3") (pinfunction "PC14-OSC32_IN_3") (pintype "unspecified"))
    )
    (net (code "116") (name "unconnected-(U1-PC15-OSC32_OUT-Pad4)") (class "Default")
      (node (ref "U1") (pin "4") (pinfunction "PC15-OSC32_OUT_4") (pintype "unspecified"))
    )
    (net (code "117") (name "unconnected-(U1-PD0-OSC_IN-Pad5)") (class "Default")
      (node (ref "U1") (pin "5") (pinfunction "PD0-OSC_IN_5") (pintype "unspecified"))
    )
    (net (code "118") (name "unconnected-(U1-PD1-OSC_OUT-Pad6)") (class "Default")
      (node (ref "U1") (pin "6") (pinfunction "PD1-OSC_OUT_6") (pintype "unspecified"))
    )
    (net (code "119") (name "unconnected-(U6-Pad2)") (class "Default")
      (node (ref "U6") (pin "2") (pinfunction "2_2") (pintype "unspecified+no_connect"))
    )
    (net (code "120") (name "unconnected-(U6-Pad3)") (class "Default")
      (node (ref "U6") (pin "3") (pinfunction "3_3") (pintype "unspecified+no_connect"))
    )
    (net (code "121") (name "unconnected-(U6-Pad4)") (class "Default")
      (node (ref "U6") (pin "4") (pinfunction "4_4") (pintype "unspecified+no_connect"))
    )
    (net (code "122") (name "unconnected-(U6-Pad5)") (class "Default")
      (node (ref "U6") (pin "5") (pinfunction "5_5") (pintype "unspecified+no_connect"))
    )
    (net (code "123") (name "unconnected-(U6-Pad7)") (class "Default")
      (node (ref "U6") (pin "7") (pinfunction "7_7") (pintype "unspecified+no_connect"))
    )
    (net (code "124") (name "unconnected-(U6-Pad8)") (class "Default")
      (node (ref "U6") (pin "8") (pinfunction "8_8") (pintype "unspecified+no_connect"))
    )
    (net (code "125") (name "unconnected-(U7-Pad2)") (class "Default")
      (node (ref "U7") (pin "2") (pinfunction "2_2") (pintype "unspecified+no_connect"))
    )
    (net (code "126") (name "unconnected-(U7-Pad3)") (class "Default")
      (node (ref "U7") (pin "3") (pinfunction "3_3") (pintype "unspecified+no_connect"))
    )
    (net (code "127") (name "unconnected-(U7-Pad4)") (class "Default")
      (node (ref "U7") (pin "4") (pinfunction "4_4") (pintype "unspecified+no_connect"))
    )
    (net (code "128") (name "unconnected-(U7-Pad5)") (class "Default")
      (node (ref "U7") (pin "5") (pinfunction "5_5") (pintype "unspecified+no_connect"))
    )
    (net (code "129") (name "unconnected-(U7-Pad7)") (class "Default")
      (node (ref "U7") (pin "7") (pinfunction "7_7") (pintype "unspecified+no_connect"))
    )
    (net (code "130") (name "unconnected-(U7-Pad8)") (class "Default")
      (node (ref "U7") (pin "8") (pinfunction "8_8") (pintype "unspecified+no_connect"))
    )
    (net (code "131") (name "unconnected-(X1-Pad5)") (class "Default")
      (node (ref "X1") (pin "5") (pinfunction "5_5") (pintype "unspecified+no_connect"))
    )
    (net (code "132") (name "unconnected-(X1-Pad6)") (class "Default")
      (node (ref "X1") (pin "6") (pinfunction "6_6") (pintype "unspecified+no_connect"))
    )
  )
)
